# Power.net
KiCad netlist of a schematic drawn in Altium Designer
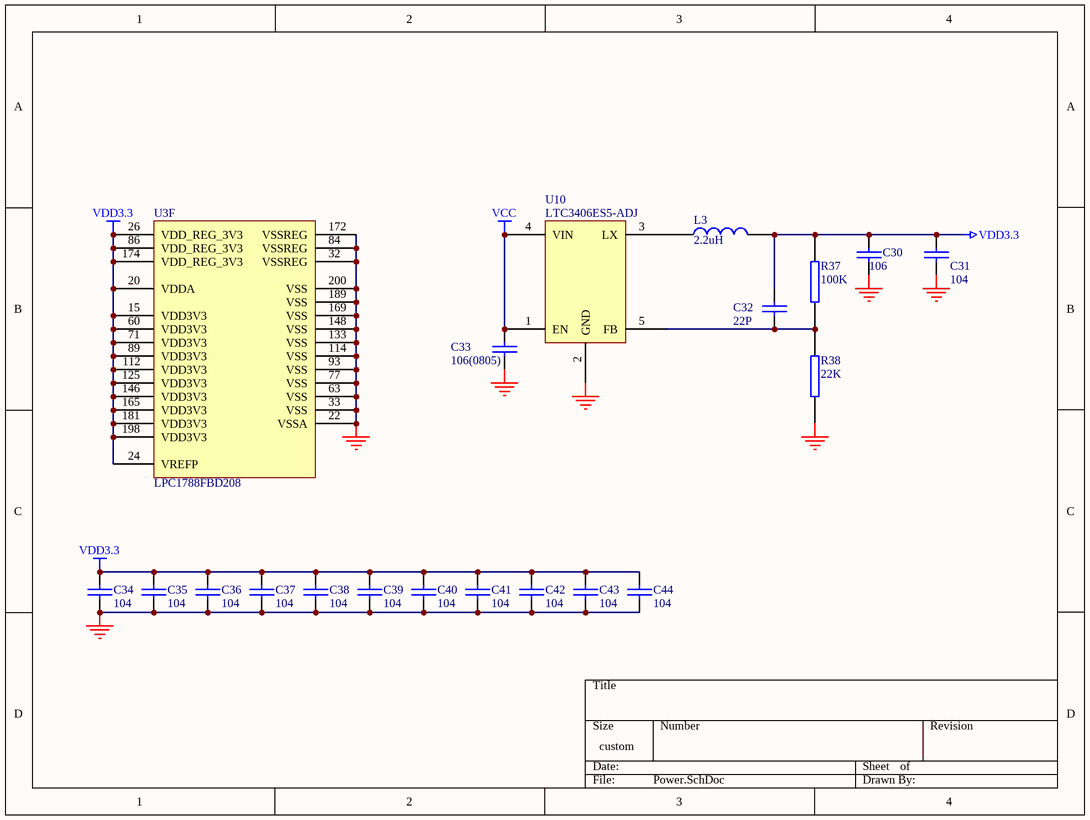
[diagram p0: Power.SchDoc]

(export (version "E")
  (design (tool "Eeschema 10.0.6"))
  (components
    (comp (ref "C30")
      (value "106")
      (footprint "C0805")
      (description "Capacitor")
      (libsource (lib "*") (part "CAP"))
    )
    (comp (ref "C31")
      (value "104")
      (footprint "C0603")
      (description "Capacitor")
      (libsource (lib "*") (part "CAP"))
    )
    (comp (ref "C32")
      (value "22P")
      (footprint "C0603")
      (description "Capacitor")
      (libsource (lib "*") (part "CAP"))
    )
    (comp (ref "C33")
      (value "106(0805)")
      (footprint "C0805")
      (description "Capacitor")
      (libsource (lib "*") (part "CAP"))
    )
    (comp (ref "C34")
      (value "104")
      (footprint "C0603")
      (description "Capacitor")
      (libsource (lib "*") (part "CAP"))
    )
    (comp (ref "C35")
      (value "104")
      (footprint "C0603")
      (description "Capacitor")
      (libsource (lib "*") (part "CAP"))
    )
    (comp (ref "C36")
      (value "104")
      (footprint "C0603")
      (description "Capacitor")
      (libsource (lib "*") (part "CAP"))
    )
    (comp (ref "C37")
      (value "104")
      (footprint "C0603")
      (description "Capacitor")
      (libsource (lib "*") (part "CAP"))
    )
    (comp (ref "C38")
      (value "104")
      (footprint "C0603")
      (description "Capacitor")
      (libsource (lib "*") (part "CAP"))
    )
    (comp (ref "C39")
      (value "104")
      (footprint "C0603")
      (description "Capacitor")
      (libsource (lib "*") (part "CAP"))
    )
    (comp (ref "C40")
      (value "104")
      (footprint "C0603")
      (description "Capacitor")
      (libsource (lib "*") (part "CAP"))
    )
    (comp (ref "C41")
      (value "104")
      (footprint "C0603")
      (description "Capacitor")
      (libsource (lib "*") (part "CAP"))
    )
    (comp (ref "C42")
      (value "104")
      (footprint "C0603")
      (description "Capacitor")
      (libsource (lib "*") (part "CAP"))
    )
    (comp (ref "C43")
      (value "104")
      (footprint "C0603")
      (description "Capacitor")
      (libsource (lib "*") (part "CAP"))
    )
    (comp (ref "C44")
      (value "104")
      (footprint "C0603")
      (description "Capacitor")
      (libsource (lib "*") (part "CAP"))
    )
    (comp (ref "L3") (value "2.2uH") (footprint "L4X4") (libsource (lib "*") (part "INDUCTOR")))
    (comp (ref "R37") (value "100K") (footprint "R0603") (libsource (lib "*") (part "RES2")))
    (comp (ref "R38") (value "22K") (footprint "R0603") (libsource (lib "*") (part "RES2")))
    (comp (ref "U3")
      (value "LPC1788FBD208")
      (footprint "QFP208")
      (libsource (lib "LPC1788") (part "LPC1788FBD208"))
    )
    (comp (ref "U10")
      (value "LTC3406ES5-ADJ")
      (footprint "SOT23-5")
      (libsource (lib "*") (part "LTC3406ES5/RT8008"))
    )
  )
  (nets
    (net (code "1") (name "GND") (class "Default")
      (node (ref "C30") (pin "2") (pinfunction "2_2") (pintype "passive"))
      (node (ref "C31") (pin "2") (pinfunction "2_2") (pintype "passive"))
      (node (ref "C33") (pin "2") (pinfunction "2_2") (pintype "passive"))
      (node (ref "C34") (pin "2") (pinfunction "2_2") (pintype "passive"))
      (node (ref "C35") (pin "2") (pinfunction "2_2") (pintype "passive"))
      (node (ref "C36") (pin "2") (pinfunction "2_2") (pintype "passive"))
      (node (ref "C37") (pin "2") (pinfunction "2_2") (pintype "passive"))
      (node (ref "C38") (pin "2") (pinfunction "2_2") (pintype "passive"))
      (node (ref "C39") (pin "2") (pinfunction "2_2") (pintype "passive"))
      (node (ref "C40") (pin "2") (pinfunction "2_2") (pintype "passive"))
      (node (ref "C41") (pin "2") (pinfunction "2_2") (pintype "passive"))
      (node (ref "C42") (pin "2") (pinfunction "2_2") (pintype "passive"))
      (node (ref "C43") (pin "2") (pinfunction "2_2") (pintype "passive"))
      (node (ref "C44") (pin "2") (pinfunction "2_2") (pintype "passive"))
      (node (ref "R38") (pin "2") (pinfunction "2_2") (pintype "passive"))
      (node (ref "U10") (pin "2") (pinfunction "GND_2") (pintype "passive"))
      (node (ref "U3") (pin "114") (pinfunction "VSS_114") (pintype "passive"))
      (node (ref "U3") (pin "133") (pinfunction "VSS_133") (pintype "passive"))
      (node (ref "U3") (pin "148") (pinfunction "VSS_148") (pintype "passive"))
      (node (ref "U3") (pin "169") (pinfunction "VSS_169") (pintype "passive"))
      (node (ref "U3") (pin "172") (pinfunction "VSSREG_172") (pintype "passive"))
      (node (ref "U3") (pin "189") (pinfunction "VSS_189") (pintype "passive"))
      (node (ref "U3") (pin "200") (pinfunction "VSS_200") (pintype "passive"))
      (node (ref "U3") (pin "22") (pinfunction "VSSA_22") (pintype "passive"))
      (node (ref "U3") (pin "32") (pinfunction "VSSREG_32") (pintype "passive"))
      (node (ref "U3") (pin "33") (pinfunction "VSS_33") (pintype "passive"))
      (node (ref "U3") (pin "63") (pinfunction "VSS_63") (pintype "passive"))
      (node (ref "U3") (pin "77") (pinfunction "VSS_77") (pintype "passive"))
      (node (ref "U3") (pin "84") (pinfunction "VSSREG_84") (pintype "passive"))
      (node (ref "U3") (pin "93") (pinfunction "VSS_93") (pintype "passive"))
    )
    (net (code "2") (name "Net-(U10-FB)") (class "Default")
      (node (ref "C32") (pin "2") (pinfunction "2_2") (pintype "passive"))
      (node (ref "R37") (pin "1") (pinfunction "1_1") (pintype "passive"))
      (node (ref "R38") (pin "1") (pinfunction "1_1") (pintype "passive"))
      (node (ref "U10") (pin "5") (pinfunction "FB_5") (pintype "passive"))
    )
    (net (code "3") (name "Net-(U10-LX)") (class "Default")
      (node (ref "L3") (pin "1") (pinfunction "1_1") (pintype "passive"))
      (node (ref "U10") (pin "3") (pinfunction "LX_3") (pintype "passive"))
    )
    (net (code "4") (name "VCC") (class "Default")
      (node (ref "C33") (pin "1") (pinfunction "1_1") (pintype "passive"))
      (node (ref "U10") (pin "1") (pinfunction "EN_1") (pintype "passive"))
      (node (ref "U10") (pin "4") (pinfunction "VIN_4") (pintype "passive"))
    )
    (net (code "5") (name "VDD3.3") (class "Default")
      (node (ref "C30") (pin "1") (pinfunction "1_1") (pintype "passive"))
      (node (ref "C31") (pin "1") (pinfunction "1_1") (pintype "passive"))
      (node (ref "C32") (pin "1") (pinfunction "1_1") (pintype "passive"))
      (node (ref "C34") (pin "1") (pinfunction "1_1") (pintype "passive"))
      (node (ref "C35") (pin "1") (pinfunction "1_1") (pintype "passive"))
      (node (ref "C36") (pin "1") (pinfunction "1_1") (pintype "passive"))
      (node (ref "C37") (pin "1") (pinfunction "1_1") (pintype "passive"))
      (node (ref "C38") (pin "1") (pinfunction "1_1") (pintype "passive"))
      (node (ref "C39") (pin "1") (pinfunction "1_1") (pintype "passive"))
      (node (ref "C40") (pin "1") (pinfunction "1_1") (pintype "passive"))
      (node (ref "C41") (pin "1") (pinfunction "1_1") (pintype "passive"))
      (node (ref "C42") (pin "1") (pinfunction "1_1") (pintype "passive"))
      (node (ref "C43") (pin "1") (pinfunction "1_1") (pintype "passive"))
      (node (ref "C44") (pin "1") (pinfunction "1_1") (pintype "passive"))
      (node (ref "L3") (pin "2") (pinfunction "2_2") (pintype "passive"))
      (node (ref "R37") (pin "2") (pinfunction "2_2") (pintype "passive"))
      (node (ref "U3") (pin "112") (pinfunction "VDD3V3_112") (pintype "passive"))
      (node (ref "U3") (pin "125") (pinfunction "VDD3V3_125") (pintype "passive"))
      (node (ref "U3") (pin "146") (pinfunction "VDD3V3_146") (pintype "passive"))
      (node (ref "U3") (pin "15") (pinfunction "VDD3V3_15") (pintype "passive"))
      (node (ref "U3") (pin "165") (pinfunction "VDD3V3_165") (pintype "passive"))
      (node (ref "U3") (pin "174") (pinfunction "VDD_REG_3V3_174") (pintype "passive"))
      (node (ref "U3") (pin "181") (pinfunction "VDD3V3_181") (pintype "passive"))
      (node (ref "U3") (pin "198") (pinfunction "VDD3V3_198") (pintype "passive"))
      (node (ref "U3") (pin "20") (pinfunction "VDDA_20") (pintype "passive"))
      (node (ref "U3") (pin "24") (pinfunction "VREFP_24") (pintype "passive"))
      (node (ref "U3") (pin "26") (pinfunction "VDD_REG_3V3_26") (pintype "passive"))
      (node (ref "U3") (pin "60") (pinfunction "VDD3V3_60") (pintype "passive"))
      (node (ref "U3") (pin "71") (pinfunction "VDD3V3_71") (pintype "passive"))
      (node (ref "U3") (pin "86") (pinfunction "VDD_REG_3V3_86") (pintype "passive"))
      (node (ref "U3") (pin "89") (pinfunction "VDD3V3_89") (pintype "passive"))
    )
  )
)
